# design.net
KiCad netlist of a schematic drawn in Altium Designer
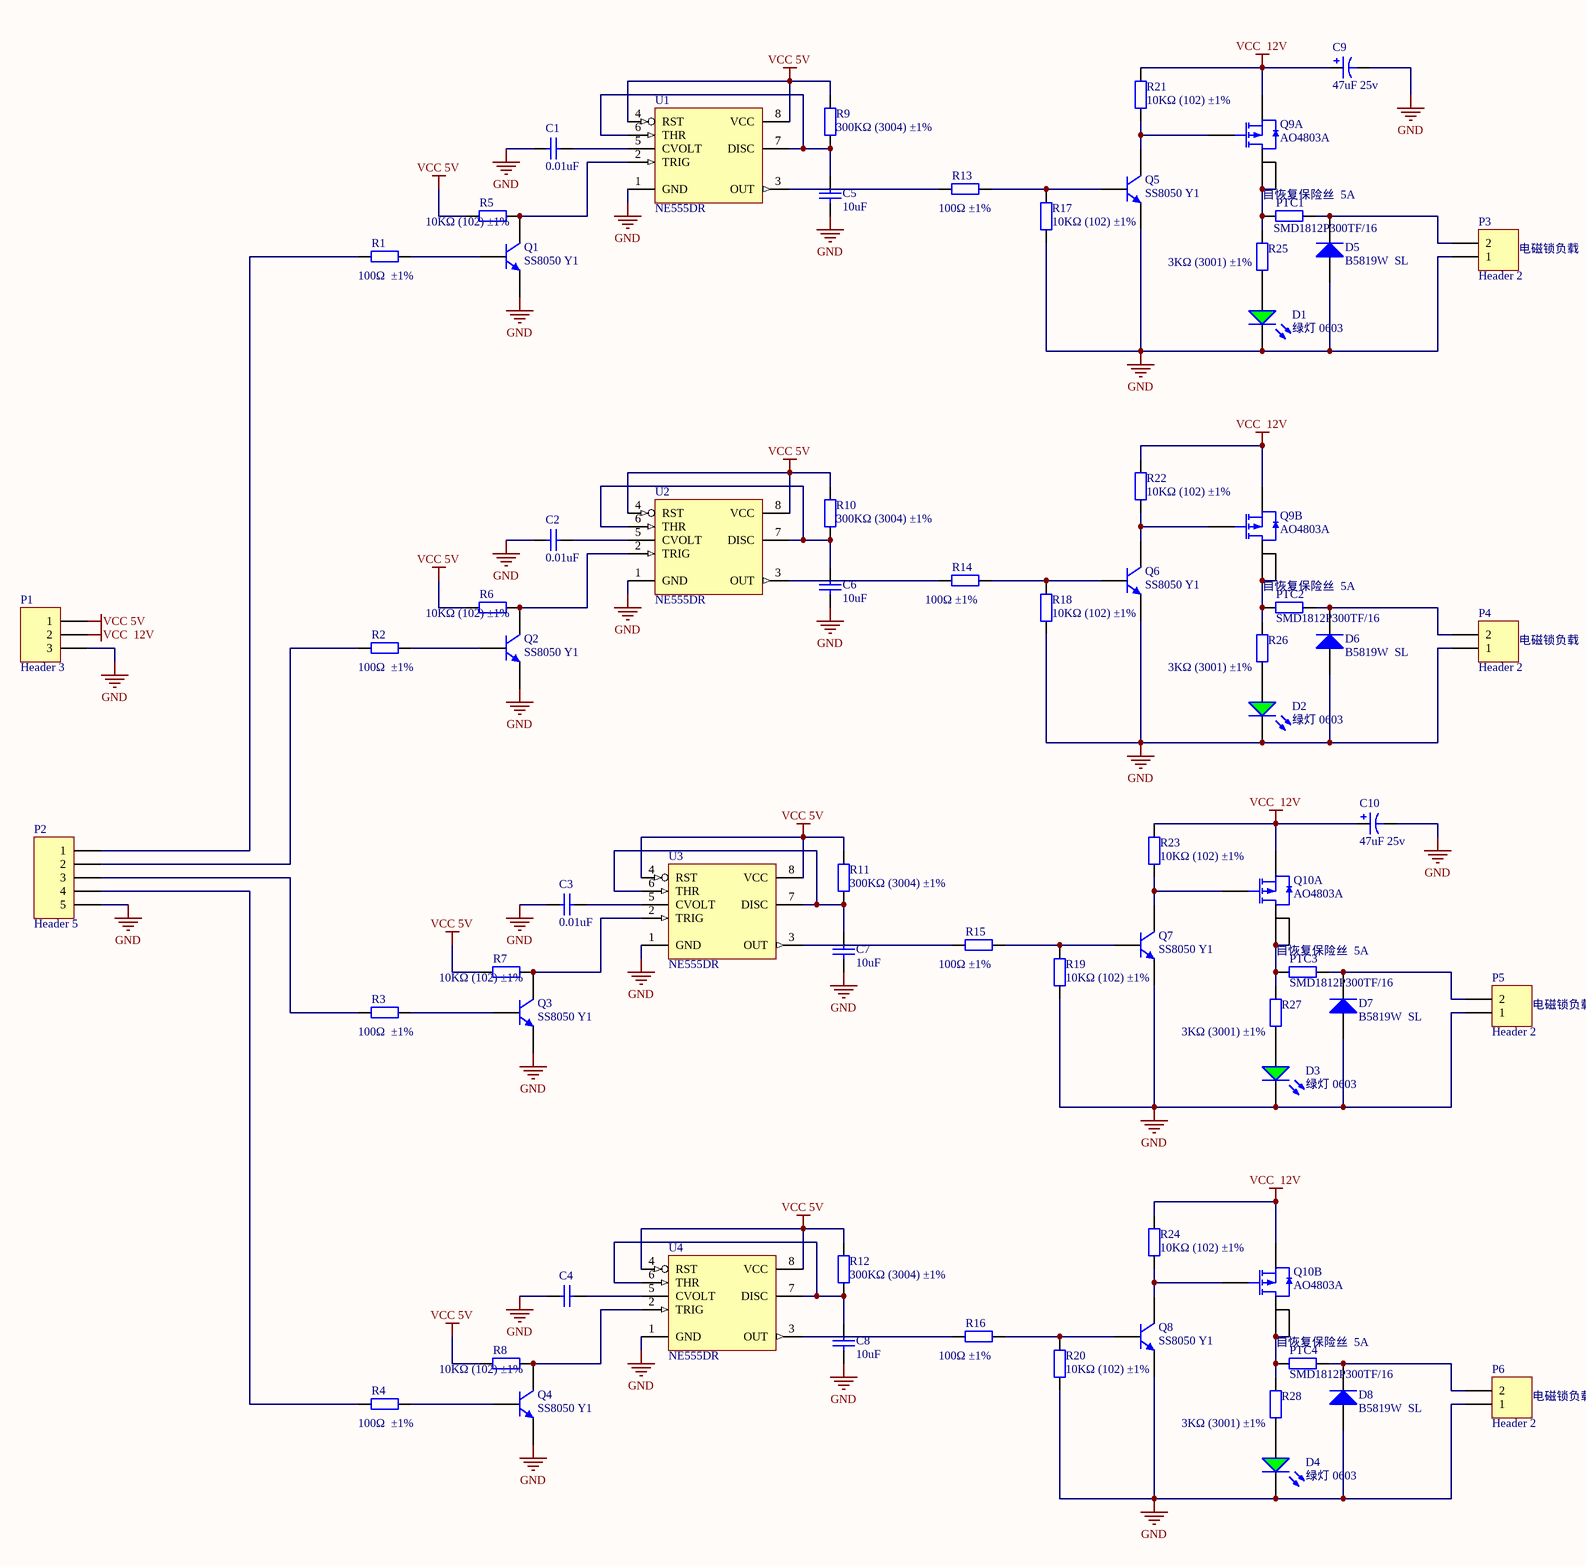
[diagram p0: 电磁阀驱动.SchDoc]

(export (version "E")
  (design (tool "Eeschema 10.0.6"))
  (components
    (comp (ref "C1")
      (value "0.01uF")
      (footprint "0603C")
      (description "Capacitor")
      (fields (field (name "PUBLISHER") "Altium Limited"))
      (libsource (lib "Miscellaneous Devices") (part "Cap"))
    )
    (comp (ref "C2")
      (value "0.01uF")
      (footprint "0603C")
      (description "Capacitor")
      (fields (field (name "PUBLISHER") "Altium Limited"))
      (libsource (lib "Miscellaneous Devices") (part "Cap"))
    )
    (comp (ref "C3")
      (value "0.01uF")
      (footprint "0603C")
      (description "Capacitor")
      (fields (field (name "PUBLISHER") "Altium Limited"))
      (libsource (lib "Miscellaneous Devices") (part "Cap"))
    )
    (comp (ref "C4")
      (value "0.01uF")
      (footprint "0603C")
      (description "Capacitor")
      (fields (field (name "PUBLISHER") "Altium Limited"))
      (libsource (lib "Miscellaneous Devices") (part "Cap"))
    )
    (comp (ref "C5")
      (value "10uF")
      (footprint "0603C")
      (description "Capacitor")
      (fields (field (name "PUBLISHER") "Altium Limited"))
      (libsource (lib "Miscellaneous Devices") (part "Cap"))
    )
    (comp (ref "C6")
      (value "10uF")
      (footprint "0603C")
      (description "Capacitor")
      (fields (field (name "PUBLISHER") "Altium Limited"))
      (libsource (lib "Miscellaneous Devices") (part "Cap"))
    )
    (comp (ref "C7")
      (value "10uF")
      (footprint "0603C")
      (description "Capacitor")
      (fields (field (name "PUBLISHER") "Altium Limited"))
      (libsource (lib "Miscellaneous Devices") (part "Cap"))
    )
    (comp (ref "C8")
      (value "10uF")
      (footprint "0603C")
      (description "Capacitor")
      (fields (field (name "PUBLISHER") "Altium Limited"))
      (libsource (lib "Miscellaneous Devices") (part "Cap"))
    )
    (comp (ref "C9")
      (value "47uF 25v")
      (footprint "CAP_SMD_6*7")
      (description "Polarized Capacitor (Radial)")
      (fields (field (name "PUBLISHER") "Altium Limited"))
      (libsource (lib "Miscellaneous Devices") (part "Cap Pol1"))
    )
    (comp (ref "C10")
      (value "47uF 25v")
      (footprint "CAP_SMD_6*7")
      (description "Polarized Capacitor (Radial)")
      (fields (field (name "PUBLISHER") "Altium Limited"))
      (libsource (lib "Miscellaneous Devices") (part "Cap Pol1"))
    )
    (comp (ref "D1")
      (value "绿灯 0603")
      (footprint "0603_LED_S1")
      (description "发光二极管")
      (libsource (lib "Miscellaneous Devices LC") (part "0603 绿灯"))
    )
    (comp (ref "D2")
      (value "绿灯 0603")
      (footprint "0603_LED_S1")
      (description "发光二极管")
      (libsource (lib "Miscellaneous Devices LC") (part "0603 绿灯"))
    )
    (comp (ref "D3")
      (value "绿灯 0603")
      (footprint "0603_LED_S1")
      (description "发光二极管")
      (libsource (lib "Miscellaneous Devices LC") (part "0603 绿灯"))
    )
    (comp (ref "D4")
      (value "绿灯 0603")
      (footprint "0603_LED_S1")
      (description "发光二极管")
      (libsource (lib "Miscellaneous Devices LC") (part "0603 绿灯"))
    )
    (comp (ref "D5")
      (value "B5819W  SL")
      (footprint "SOD-123")
      (description "肖特基二极管")
      (libsource (lib "Miscellaneous Devices LC") (part "SOD-123 B5819W  SL"))
    )
    (comp (ref "D6")
      (value "B5819W  SL")
      (footprint "SOD-123")
      (description "肖特基二极管")
      (libsource (lib "Miscellaneous Devices LC") (part "SOD-123 B5819W  SL"))
    )
    (comp (ref "D7")
      (value "B5819W  SL")
      (footprint "SOD-123")
      (description "肖特基二极管")
      (libsource (lib "Miscellaneous Devices LC") (part "SOD-123 B5819W  SL"))
    )
    (comp (ref "D8")
      (value "B5819W  SL")
      (footprint "SOD-123")
      (description "肖特基二极管")
      (libsource (lib "Miscellaneous Devices LC") (part "SOD-123 B5819W  SL"))
    )
    (comp (ref "P1")
      (value "Header 3")
      (footprint "sip-3")
      (description "Header, 3-Pin")
      (fields (field (name "PUBLISHER") "Altium Limited"))
      (libsource (lib "Miscellaneous Connectors") (part "Header 3"))
    )
    (comp (ref "P2")
      (value "Header 5")
      (footprint "SIP-5")
      (description "Header, 5-Pin")
      (fields (field (name "PUBLISHER") "Altium Limited"))
      (libsource (lib "Miscellaneous Connectors") (part "Header 5"))
    )
    (comp (ref "P3")
      (value "Header 2")
      (footprint "SIP-2")
      (description "Header, 2-Pin")
      (fields (field (name "PUBLISHER") "Altium Limited"))
      (libsource (lib "Miscellaneous Connectors") (part "Header 2"))
    )
    (comp (ref "P4")
      (value "Header 2")
      (footprint "SIP-2")
      (description "Header, 2-Pin")
      (fields (field (name "PUBLISHER") "Altium Limited"))
      (libsource (lib "Miscellaneous Connectors") (part "Header 2"))
    )
    (comp (ref "P5")
      (value "Header 2")
      (footprint "SIP-2")
      (description "Header, 2-Pin")
      (fields (field (name "PUBLISHER") "Altium Limited"))
      (libsource (lib "Miscellaneous Connectors") (part "Header 2"))
    )
    (comp (ref "P6")
      (value "Header 2")
      (footprint "SIP-2")
      (description "Header, 2-Pin")
      (fields (field (name "PUBLISHER") "Altium Limited"))
      (libsource (lib "Miscellaneous Connectors") (part "Header 2"))
    )
    (comp (ref "PTC1")
      (value "SMD1812P300TF/16")
      (footprint "1812")
      (description "自恢复保险丝")
      (libsource (lib "") (part "0603 3KΩ (3001) 1%_1"))
    )
    (comp (ref "PTC2")
      (value "SMD1812P300TF/16")
      (footprint "1812")
      (description "自恢复保险丝")
      (libsource (lib "") (part "0603 3KΩ (3001) 1%_1"))
    )
    (comp (ref "PTC3")
      (value "SMD1812P300TF/16")
      (footprint "1812")
      (description "自恢复保险丝")
      (libsource (lib "") (part "0603 3KΩ (3001) 1%_1"))
    )
    (comp (ref "PTC4")
      (value "SMD1812P300TF/16")
      (footprint "1812")
      (description "自恢复保险丝")
      (libsource (lib "") (part "0603 3KΩ (3001) 1%_1"))
    )
    (comp (ref "Q1")
      (value "SS8050 Y1")
      (footprint "SOT-23(SOT-23-3)")
      (description "三极管")
      (libsource (lib "Miscellaneous Devices LC") (part "SOT-23 SS8050 Y1"))
    )
    (comp (ref "Q2")
      (value "SS8050 Y1")
      (footprint "SOT-23(SOT-23-3)")
      (description "三极管")
      (libsource (lib "Miscellaneous Devices LC") (part "SOT-23 SS8050 Y1"))
    )
    (comp (ref "Q3")
      (value "SS8050 Y1")
      (footprint "SOT-23(SOT-23-3)")
      (description "三极管")
      (libsource (lib "Miscellaneous Devices LC") (part "SOT-23 SS8050 Y1"))
    )
    (comp (ref "Q4")
      (value "SS8050 Y1")
      (footprint "SOT-23(SOT-23-3)")
      (description "三极管")
      (libsource (lib "Miscellaneous Devices LC") (part "SOT-23 SS8050 Y1"))
    )
    (comp (ref "Q5")
      (value "SS8050 Y1")
      (footprint "SOT-23(SOT-23-3)")
      (description "三极管")
      (libsource (lib "Miscellaneous Devices LC") (part "SOT-23 SS8050 Y1"))
    )
    (comp (ref "Q6")
      (value "SS8050 Y1")
      (footprint "SOT-23(SOT-23-3)")
      (description "三极管")
      (libsource (lib "Miscellaneous Devices LC") (part "SOT-23 SS8050 Y1"))
    )
    (comp (ref "Q7")
      (value "SS8050 Y1")
      (footprint "SOT-23(SOT-23-3)")
      (description "三极管")
      (libsource (lib "Miscellaneous Devices LC") (part "SOT-23 SS8050 Y1"))
    )
    (comp (ref "Q8")
      (value "SS8050 Y1")
      (footprint "SOT-23(SOT-23-3)")
      (description "三极管")
      (libsource (lib "Miscellaneous Devices LC") (part "SOT-23 SS8050 Y1"))
    )
    (comp (ref "Q9")
      (value "AO4803A")
      (footprint "SOP-8_150mil")
      (description "MOS(场效应管)")
      (libsource (lib "Miscellaneous Devices LC") (part "APM4953KC-TRG"))
    )
    (comp (ref "Q10")
      (value "AO4803A")
      (footprint "SOP-8_150mil")
      (description "MOS(场效应管)")
      (libsource (lib "Miscellaneous Devices LC") (part "APM4953KC-TRG"))
    )
    (comp (ref "R1")
      (value "100Ω  ±1%")
      (footprint "0603_R")
      (description "贴片电阻")
      (libsource (lib "Miscellaneous Devices LC") (part "0603 3KΩ (3001) 1%"))
    )
    (comp (ref "R2")
      (value "100Ω  ±1%")
      (footprint "0603_R")
      (description "贴片电阻")
      (libsource (lib "Miscellaneous Devices LC") (part "0603 3KΩ (3001) 1%"))
    )
    (comp (ref "R3")
      (value "100Ω  ±1%")
      (footprint "0603_R")
      (description "贴片电阻")
      (libsource (lib "Miscellaneous Devices LC") (part "0603 3KΩ (3001) 1%"))
    )
    (comp (ref "R4")
      (value "100Ω  ±1%")
      (footprint "0603_R")
      (description "贴片电阻")
      (libsource (lib "Miscellaneous Devices LC") (part "0603 3KΩ (3001) 1%"))
    )
    (comp (ref "R5")
      (value "10KΩ (102) ±1%")
      (footprint "0603_R")
      (description "贴片电阻")
      (libsource (lib "Miscellaneous Devices LC") (part "0603 3KΩ (3001) 1%"))
    )
    (comp (ref "R6")
      (value "10KΩ (102) ±1%")
      (footprint "0603_R")
      (description "贴片电阻")
      (libsource (lib "Miscellaneous Devices LC") (part "0603 3KΩ (3001) 1%"))
    )
    (comp (ref "R7")
      (value "10KΩ (102) ±1%")
      (footprint "0603_R")
      (description "贴片电阻")
      (libsource (lib "Miscellaneous Devices LC") (part "0603 3KΩ (3001) 1%"))
    )
    (comp (ref "R8")
      (value "10KΩ (102) ±1%")
      (footprint "0603_R")
      (description "贴片电阻")
      (libsource (lib "Miscellaneous Devices LC") (part "0603 3KΩ (3001) 1%"))
    )
    (comp (ref "R9")
      (value "300KΩ (3004) ±1%")
      (footprint "0603_R")
      (description "贴片电阻")
      (libsource (lib "") (part "0603 3KΩ (3001) 1%_2"))
    )
    (comp (ref "R10")
      (value "300KΩ (3004) ±1%")
      (footprint "0603_R")
      (description "贴片电阻")
      (libsource (lib "") (part "0603 3KΩ (3001) 1%_2"))
    )
    (comp (ref "R11")
      (value "300KΩ (3004) ±1%")
      (footprint "0603_R")
      (description "贴片电阻")
      (libsource (lib "") (part "0603 3KΩ (3001) 1%_2"))
    )
    (comp (ref "R12")
      (value "300KΩ (3004) ±1%")
      (footprint "0603_R")
      (description "贴片电阻")
      (libsource (lib "") (part "0603 3KΩ (3001) 1%_2"))
    )
    (comp (ref "R13")
      (value "100Ω ±1%")
      (footprint "0603_R")
      (description "贴片电阻")
      (libsource (lib "") (part "0603 3KΩ (3001) 1%_1"))
    )
    (comp (ref "R14")
      (value "100Ω ±1%")
      (footprint "0603_R")
      (description "贴片电阻")
      (libsource (lib "") (part "0603 3KΩ (3001) 1%_1"))
    )
    (comp (ref "R15")
      (value "100Ω ±1%")
      (footprint "0603_R")
      (description "贴片电阻")
      (libsource (lib "") (part "0603 3KΩ (3001) 1%_1"))
    )
    (comp (ref "R16")
      (value "100Ω ±1%")
      (footprint "0603_R")
      (description "贴片电阻")
      (libsource (lib "") (part "0603 3KΩ (3001) 1%_1"))
    )
    (comp (ref "R17")
      (value "10KΩ (102) ±1%")
      (footprint "0603_R")
      (description "贴片电阻")
      (libsource (lib "") (part "0603 3KΩ (3001) 1%_3"))
    )
    (comp (ref "R18")
      (value "10KΩ (102) ±1%")
      (footprint "0603_R")
      (description "贴片电阻")
      (libsource (lib "") (part "0603 3KΩ (3001) 1%_3"))
    )
    (comp (ref "R19")
      (value "10KΩ (102) ±1%")
      (footprint "0603_R")
      (description "贴片电阻")
      (libsource (lib "") (part "0603 3KΩ (3001) 1%_3"))
    )
    (comp (ref "R20")
      (value "10KΩ (102) ±1%")
      (footprint "0603_R")
      (description "贴片电阻")
      (libsource (lib "") (part "0603 3KΩ (3001) 1%_3"))
    )
    (comp (ref "R21")
      (value "10KΩ (102) ±1%")
      (footprint "0603_R")
      (description "贴片电阻")
      (libsource (lib "") (part "0603 3KΩ (3001) 1%_3"))
    )
    (comp (ref "R22")
      (value "10KΩ (102) ±1%")
      (footprint "0603_R")
      (description "贴片电阻")
      (libsource (lib "") (part "0603 3KΩ (3001) 1%_3"))
    )
    (comp (ref "R23")
      (value "10KΩ (102) ±1%")
      (footprint "0603_R")
      (description "贴片电阻")
      (libsource (lib "") (part "0603 3KΩ (3001) 1%_3"))
    )
    (comp (ref "R24")
      (value "10KΩ (102) ±1%")
      (footprint "0603_R")
      (description "贴片电阻")
      (libsource (lib "") (part "0603 3KΩ (3001) 1%_3"))
    )
    (comp (ref "R25")
      (value "3KΩ (3001) ±1%")
      (footprint "0603_R")
      (description "贴片电阻")
      (libsource (lib "") (part "0603 3KΩ (3001) 1%_2"))
    )
    (comp (ref "R26")
      (value "3KΩ (3001) ±1%")
      (footprint "0603_R")
      (description "贴片电阻")
      (libsource (lib "") (part "0603 3KΩ (3001) 1%_2"))
    )
    (comp (ref "R27")
      (value "3KΩ (3001) ±1%")
      (footprint "0603_R")
      (description "贴片电阻")
      (libsource (lib "") (part "0603 3KΩ (3001) 1%_2"))
    )
    (comp (ref "R28")
      (value "3KΩ (3001) ±1%")
      (footprint "0603_R")
      (description "贴片电阻")
      (libsource (lib "") (part "0603 3KΩ (3001) 1%_2"))
    )
    (comp (ref "U1")
      (value "NE555DR")
      (footprint "SOIC-8_150mil")
      (description "时基集成")
      (libsource (lib "Miscellaneous Devices LC") (part "NE555DR_[C7593]"))
    )
    (comp (ref "U2")
      (value "NE555DR")
      (footprint "SOIC-8_150mil")
      (description "时基集成")
      (libsource (lib "Miscellaneous Devices LC") (part "NE555DR_[C7593]"))
    )
    (comp (ref "U3")
      (value "NE555DR")
      (footprint "SOIC-8_150mil")
      (description "时基集成")
      (libsource (lib "Miscellaneous Devices LC") (part "NE555DR_[C7593]"))
    )
    (comp (ref "U4")
      (value "NE555DR")
      (footprint "SOIC-8_150mil")
      (description "时基集成")
      (libsource (lib "Miscellaneous Devices LC") (part "NE555DR_[C7593]"))
    )
  )
  (nets
    (net (code "1") (name "GND") (class "Default")
      (node (ref "C1") (pin "1") (pinfunction "1_1") (pintype "passive"))
      (node (ref "C10") (pin "2") (pinfunction "2_2") (pintype "passive"))
      (node (ref "C2") (pin "1") (pinfunction "1_1") (pintype "passive"))
      (node (ref "C3") (pin "1") (pinfunction "1_1") (pintype "passive"))
      (node (ref "C4") (pin "1") (pinfunction "1_1") (pintype "passive"))
      (node (ref "C5") (pin "1") (pinfunction "1_1") (pintype "passive"))
      (node (ref "C6") (pin "1") (pinfunction "1_1") (pintype "passive"))
      (node (ref "C7") (pin "1") (pinfunction "1_1") (pintype "passive"))
      (node (ref "C8") (pin "1") (pinfunction "1_1") (pintype "passive"))
      (node (ref "C9") (pin "2") (pinfunction "2_2") (pintype "passive"))
      (node (ref "D1") (pin "K") (pinfunction "K_K") (pintype "passive"))
      (node (ref "D2") (pin "K") (pinfunction "K_K") (pintype "passive"))
      (node (ref "D3") (pin "K") (pinfunction "K_K") (pintype "passive"))
      (node (ref "D4") (pin "K") (pinfunction "K_K") (pintype "passive"))
      (node (ref "D5") (pin "1") (pinfunction "A_1") (pintype "passive"))
      (node (ref "D6") (pin "1") (pinfunction "A_1") (pintype "passive"))
      (node (ref "D7") (pin "1") (pinfunction "A_1") (pintype "passive"))
      (node (ref "D8") (pin "1") (pinfunction "A_1") (pintype "passive"))
      (node (ref "P1") (pin "3") (pinfunction "3_3") (pintype "passive"))
      (node (ref "P2") (pin "5") (pinfunction "5_5") (pintype "passive"))
      (node (ref "P3") (pin "1") (pinfunction "1_1") (pintype "passive"))
      (node (ref "P4") (pin "1") (pinfunction "1_1") (pintype "passive"))
      (node (ref "P5") (pin "1") (pinfunction "1_1") (pintype "passive"))
      (node (ref "P6") (pin "1") (pinfunction "1_1") (pintype "passive"))
      (node (ref "Q1") (pin "2") (pinfunction "E_2") (pintype "passive"))
      (node (ref "Q2") (pin "2") (pinfunction "E_2") (pintype "passive"))
      (node (ref "Q3") (pin "2") (pinfunction "E_2") (pintype "passive"))
      (node (ref "Q4") (pin "2") (pinfunction "E_2") (pintype "passive"))
      (node (ref "Q5") (pin "2") (pinfunction "E_2") (pintype "passive"))
      (node (ref "Q6") (pin "2") (pinfunction "E_2") (pintype "passive"))
      (node (ref "Q7") (pin "2") (pinfunction "E_2") (pintype "passive"))
      (node (ref "Q8") (pin "2") (pinfunction "E_2") (pintype "passive"))
      (node (ref "R17") (pin "1") (pinfunction "1_1") (pintype "passive"))
      (node (ref "R18") (pin "1") (pinfunction "1_1") (pintype "passive"))
      (node (ref "R19") (pin "1") (pinfunction "1_1") (pintype "passive"))
      (node (ref "R20") (pin "1") (pinfunction "1_1") (pintype "passive"))
      (node (ref "U1") (pin "1") (pinfunction "GND_1") (pintype "power_in"))
      (node (ref "U2") (pin "1") (pinfunction "GND_1") (pintype "power_in"))
      (node (ref "U3") (pin "1") (pinfunction "GND_1") (pintype "power_in"))
      (node (ref "U4") (pin "1") (pinfunction "GND_1") (pintype "power_in"))
    )
    (net (code "2") (name "Net-(D1-PadA)") (class "Default")
      (node (ref "D1") (pin "A") (pinfunction "A_A") (pintype "passive"))
      (node (ref "R25") (pin "2") (pinfunction "2_2") (pintype "passive"))
    )
    (net (code "3") (name "Net-(D2-PadA)") (class "Default")
      (node (ref "D2") (pin "A") (pinfunction "A_A") (pintype "passive"))
      (node (ref "R26") (pin "2") (pinfunction "2_2") (pintype "passive"))
    )
    (net (code "4") (name "Net-(D3-PadA)") (class "Default")
      (node (ref "D3") (pin "A") (pinfunction "A_A") (pintype "passive"))
      (node (ref "R27") (pin "2") (pinfunction "2_2") (pintype "passive"))
    )
    (net (code "5") (name "Net-(D4-PadA)") (class "Default")
      (node (ref "D4") (pin "A") (pinfunction "A_A") (pintype "passive"))
      (node (ref "R28") (pin "2") (pinfunction "2_2") (pintype "passive"))
    )
    (net (code "6") (name "Net-(D5-K)") (class "Default")
      (node (ref "D5") (pin "2") (pinfunction "K_2") (pintype "passive"))
      (node (ref "P3") (pin "2") (pinfunction "2_2") (pintype "passive"))
      (node (ref "PTC1") (pin "2") (pinfunction "2_2") (pintype "passive"))
    )
    (net (code "7") (name "Net-(D6-K)") (class "Default")
      (node (ref "D6") (pin "2") (pinfunction "K_2") (pintype "passive"))
      (node (ref "P4") (pin "2") (pinfunction "2_2") (pintype "passive"))
      (node (ref "PTC2") (pin "2") (pinfunction "2_2") (pintype "passive"))
    )
    (net (code "8") (name "Net-(D7-K)") (class "Default")
      (node (ref "D7") (pin "2") (pinfunction "K_2") (pintype "passive"))
      (node (ref "P5") (pin "2") (pinfunction "2_2") (pintype "passive"))
      (node (ref "PTC3") (pin "2") (pinfunction "2_2") (pintype "passive"))
    )
    (net (code "9") (name "Net-(D8-K)") (class "Default")
      (node (ref "D8") (pin "2") (pinfunction "K_2") (pintype "passive"))
      (node (ref "P6") (pin "2") (pinfunction "2_2") (pintype "passive"))
      (node (ref "PTC4") (pin "2") (pinfunction "2_2") (pintype "passive"))
    )
    (net (code "10") (name "Net-(P2-Pad1)") (class "Default")
      (node (ref "P2") (pin "1") (pinfunction "1_1") (pintype "passive"))
      (node (ref "R1") (pin "2") (pinfunction "2_2") (pintype "passive"))
    )
    (net (code "11") (name "Net-(P2-Pad2)") (class "Default")
      (node (ref "P2") (pin "2") (pinfunction "2_2") (pintype "passive"))
      (node (ref "R2") (pin "2") (pinfunction "2_2") (pintype "passive"))
    )
    (net (code "12") (name "Net-(P2-Pad3)") (class "Default")
      (node (ref "P2") (pin "3") (pinfunction "3_3") (pintype "passive"))
      (node (ref "R3") (pin "2") (pinfunction "2_2") (pintype "passive"))
    )
    (net (code "13") (name "Net-(P2-Pad4)") (class "Default")
      (node (ref "P2") (pin "4") (pinfunction "4_4") (pintype "passive"))
      (node (ref "R4") (pin "2") (pinfunction "2_2") (pintype "passive"))
    )
    (net (code "14") (name "Net-(PTC1-Pad1)") (class "Default")
      (node (ref "PTC1") (pin "1") (pinfunction "1_1") (pintype "passive"))
      (node (ref "Q9") (pin "7") (pinfunction "D_7") (pintype "passive"))
      (node (ref "Q9") (pin "8") (pinfunction "D_8") (pintype "passive"))
      (node (ref "R25") (pin "1") (pinfunction "1_1") (pintype "passive"))
    )
    (net (code "15") (name "Net-(PTC2-Pad1)") (class "Default")
      (node (ref "PTC2") (pin "1") (pinfunction "1_1") (pintype "passive"))
      (node (ref "Q9") (pin "5") (pinfunction "D_5") (pintype "passive"))
      (node (ref "Q9") (pin "6") (pinfunction "D_6") (pintype "passive"))
      (node (ref "R26") (pin "1") (pinfunction "1_1") (pintype "passive"))
    )
    (net (code "16") (name "Net-(PTC3-Pad1)") (class "Default")
      (node (ref "PTC3") (pin "1") (pinfunction "1_1") (pintype "passive"))
      (node (ref "Q10") (pin "7") (pinfunction "D_7") (pintype "passive"))
      (node (ref "Q10") (pin "8") (pinfunction "D_8") (pintype "passive"))
      (node (ref "R27") (pin "1") (pinfunction "1_1") (pintype "passive"))
    )
    (net (code "17") (name "Net-(PTC4-Pad1)") (class "Default")
      (node (ref "PTC4") (pin "1") (pinfunction "1_1") (pintype "passive"))
      (node (ref "Q10") (pin "5") (pinfunction "D_5") (pintype "passive"))
      (node (ref "Q10") (pin "6") (pinfunction "D_6") (pintype "passive"))
      (node (ref "R28") (pin "1") (pinfunction "1_1") (pintype "passive"))
    )
    (net (code "18") (name "Net-(Q1-B)") (class "Default")
      (node (ref "Q1") (pin "1") (pinfunction "B_1") (pintype "passive"))
      (node (ref "R1") (pin "1") (pinfunction "1_1") (pintype "passive"))
    )
    (net (code "19") (name "Net-(Q1-C)") (class "Default")
      (node (ref "Q1") (pin "3") (pinfunction "C_3") (pintype "passive"))
      (node (ref "R5") (pin "1") (pinfunction "1_1") (pintype "passive"))
      (node (ref "U1") (pin "2") (pinfunction "TRIG_2") (pintype "input"))
    )
    (net (code "20") (name "Net-(Q2-B)") (class "Default")
      (node (ref "Q2") (pin "1") (pinfunction "B_1") (pintype "passive"))
      (node (ref "R2") (pin "1") (pinfunction "1_1") (pintype "passive"))
    )
    (net (code "21") (name "Net-(Q2-C)") (class "Default")
      (node (ref "Q2") (pin "3") (pinfunction "C_3") (pintype "passive"))
      (node (ref "R6") (pin "1") (pinfunction "1_1") (pintype "passive"))
      (node (ref "U2") (pin "2") (pinfunction "TRIG_2") (pintype "input"))
    )
    (net (code "22") (name "Net-(Q3-B)") (class "Default")
      (node (ref "Q3") (pin "1") (pinfunction "B_1") (pintype "passive"))
      (node (ref "R3") (pin "1") (pinfunction "1_1") (pintype "passive"))
    )
    (net (code "23") (name "Net-(Q3-C)") (class "Default")
      (node (ref "Q3") (pin "3") (pinfunction "C_3") (pintype "passive"))
      (node (ref "R7") (pin "1") (pinfunction "1_1") (pintype "passive"))
      (node (ref "U3") (pin "2") (pinfunction "TRIG_2") (pintype "input"))
    )
    (net (code "24") (name "Net-(Q4-B)") (class "Default")
      (node (ref "Q4") (pin "1") (pinfunction "B_1") (pintype "passive"))
      (node (ref "R4") (pin "1") (pinfunction "1_1") (pintype "passive"))
    )
    (net (code "25") (name "Net-(Q4-C)") (class "Default")
      (node (ref "Q4") (pin "3") (pinfunction "C_3") (pintype "passive"))
      (node (ref "R8") (pin "1") (pinfunction "1_1") (pintype "passive"))
      (node (ref "U4") (pin "2") (pinfunction "TRIG_2") (pintype "input"))
    )
    (net (code "26") (name "Net-(Q5-B)") (class "Default")
      (node (ref "Q5") (pin "1") (pinfunction "B_1") (pintype "passive"))
      (node (ref "R13") (pin "2") (pinfunction "2_2") (pintype "passive"))
      (node (ref "R17") (pin "2") (pinfunction "2_2") (pintype "passive"))
    )
    (net (code "27") (name "Net-(Q5-C)") (class "Default")
      (node (ref "Q5") (pin "3") (pinfunction "C_3") (pintype "passive"))
      (node (ref "Q9") (pin "2") (pinfunction "G_2") (pintype "passive"))
      (node (ref "R21") (pin "1") (pinfunction "1_1") (pintype "passive"))
    )
    (net (code "28") (name "Net-(Q6-B)") (class "Default")
      (node (ref "Q6") (pin "1") (pinfunction "B_1") (pintype "passive"))
      (node (ref "R14") (pin "2") (pinfunction "2_2") (pintype "passive"))
      (node (ref "R18") (pin "2") (pinfunction "2_2") (pintype "passive"))
    )
    (net (code "29") (name "Net-(Q6-C)") (class "Default")
      (node (ref "Q6") (pin "3") (pinfunction "C_3") (pintype "passive"))
      (node (ref "Q9") (pin "4") (pinfunction "G_4") (pintype "passive"))
      (node (ref "R22") (pin "1") (pinfunction "1_1") (pintype "passive"))
    )
    (net (code "30") (name "Net-(Q7-B)") (class "Default")
      (node (ref "Q7") (pin "1") (pinfunction "B_1") (pintype "passive"))
      (node (ref "R15") (pin "2") (pinfunction "2_2") (pintype "passive"))
      (node (ref "R19") (pin "2") (pinfunction "2_2") (pintype "passive"))
    )
    (net (code "31") (name "Net-(Q8-B)") (class "Default")
      (node (ref "Q8") (pin "1") (pinfunction "B_1") (pintype "passive"))
      (node (ref "R16") (pin "2") (pinfunction "2_2") (pintype "passive"))
      (node (ref "R20") (pin "2") (pinfunction "2_2") (pintype "passive"))
    )
    (net (code "32") (name "Net-(Q10A-G)") (class "Default")
      (node (ref "Q10") (pin "2") (pinfunction "G_2") (pintype "passive"))
      (node (ref "Q7") (pin "3") (pinfunction "C_3") (pintype "passive"))
      (node (ref "R23") (pin "1") (pinfunction "1_1") (pintype "passive"))
    )
    (net (code "33") (name "Net-(Q10B-G)") (class "Default")
      (node (ref "Q10") (pin "4") (pinfunction "G_4") (pintype "passive"))
      (node (ref "Q8") (pin "3") (pinfunction "C_3") (pintype "passive"))
      (node (ref "R24") (pin "1") (pinfunction "1_1") (pintype "passive"))
    )
    (net (code "34") (name "Net-(U1-CVOLT)") (class "Default")
      (node (ref "C1") (pin "2") (pinfunction "2_2") (pintype "passive"))
      (node (ref "U1") (pin "5") (pinfunction "CVOLT_5") (pintype "passive"))
    )
    (net (code "35") (name "Net-(U1-DISC)") (class "Default")
      (node (ref "C5") (pin "2") (pinfunction "2_2") (pintype "passive"))
      (node (ref "R9") (pin "2") (pinfunction "2_2") (pintype "passive"))
      (node (ref "U1") (pin "6") (pinfunction "THR_6") (pintype "input"))
      (node (ref "U1") (pin "7") (pinfunction "DISC_7") (pintype "open_collector"))
    )
    (net (code "36") (name "Net-(U1-OUT)") (class "Default")
      (node (ref "R13") (pin "1") (pinfunction "1_1") (pintype "passive"))
      (node (ref "U1") (pin "3") (pinfunction "OUT_3") (pintype "output"))
    )
    (net (code "37") (name "Net-(U2-CVOLT)") (class "Default")
      (node (ref "C2") (pin "2") (pinfunction "2_2") (pintype "passive"))
      (node (ref "U2") (pin "5") (pinfunction "CVOLT_5") (pintype "passive"))
    )
    (net (code "38") (name "Net-(U2-DISC)") (class "Default")
      (node (ref "C6") (pin "2") (pinfunction "2_2") (pintype "passive"))
      (node (ref "R10") (pin "2") (pinfunction "2_2") (pintype "passive"))
      (node (ref "U2") (pin "6") (pinfunction "THR_6") (pintype "input"))
      (node (ref "U2") (pin "7") (pinfunction "DISC_7") (pintype "open_collector"))
    )
    (net (code "39") (name "Net-(U2-OUT)") (class "Default")
      (node (ref "R14") (pin "1") (pinfunction "1_1") (pintype "passive"))
      (node (ref "U2") (pin "3") (pinfunction "OUT_3") (pintype "output"))
    )
    (net (code "40") (name "Net-(U3-CVOLT)") (class "Default")
      (node (ref "C3") (pin "2") (pinfunction "2_2") (pintype "passive"))
      (node (ref "U3") (pin "5") (pinfunction "CVOLT_5") (pintype "passive"))
    )
    (net (code "41") (name "Net-(U3-DISC)") (class "Default")
      (node (ref "C7") (pin "2") (pinfunction "2_2") (pintype "passive"))
      (node (ref "R11") (pin "2") (pinfunction "2_2") (pintype "passive"))
      (node (ref "U3") (pin "6") (pinfunction "THR_6") (pintype "input"))
      (node (ref "U3") (pin "7") (pinfunction "DISC_7") (pintype "open_collector"))
    )
    (net (code "42") (name "Net-(U3-OUT)") (class "Default")
      (node (ref "R15") (pin "1") (pinfunction "1_1") (pintype "passive"))
      (node (ref "U3") (pin "3") (pinfunction "OUT_3") (pintype "output"))
    )
    (net (code "43") (name "Net-(U4-CVOLT)") (class "Default")
      (node (ref "C4") (pin "2") (pinfunction "2_2") (pintype "passive"))
      (node (ref "U4") (pin "5") (pinfunction "CVOLT_5") (pintype "passive"))
    )
    (net (code "44") (name "Net-(U4-DISC)") (class "Default")
      (node (ref "C8") (pin "2") (pinfunction "2_2") (pintype "passive"))
      (node (ref "R12") (pin "2") (pinfunction "2_2") (pintype "passive"))
      (node (ref "U4") (pin "6") (pinfunction "THR_6") (pintype "input"))
      (node (ref "U4") (pin "7") (pinfunction "DISC_7") (pintype "open_collector"))
    )
    (net (code "45") (name "Net-(U4-OUT)") (class "Default")
      (node (ref "R16") (pin "1") (pinfunction "1_1") (pintype "passive"))
      (node (ref "U4") (pin "3") (pinfunction "OUT_3") (pintype "output"))
    )
    (net (code "46") (name "VCC  12V") (class "Default")
      (node (ref "C10") (pin "1") (pinfunction "1_1") (pintype "passive"))
      (node (ref "C9") (pin "1") (pinfunction "1_1") (pintype "passive"))
      (node (ref "P1") (pin "2") (pinfunction "2_2") (pintype "passive"))
      (node (ref "Q10") (pin "1") (pinfunction "S_1") (pintype "passive"))
      (node (ref "Q10") (pin "3") (pinfunction "S_3") (pintype "passive"))
      (node (ref "Q9") (pin "1") (pinfunction "S_1") (pintype "passive"))
      (node (ref "Q9") (pin "3") (pinfunction "S_3") (pintype "passive"))
      (node (ref "R21") (pin "2") (pinfunction "2_2") (pintype "passive"))
      (node (ref "R22") (pin "2") (pinfunction "2_2") (pintype "passive"))
      (node (ref "R23") (pin "2") (pinfunction "2_2") (pintype "passive"))
      (node (ref "R24") (pin "2") (pinfunction "2_2") (pintype "passive"))
    )
    (net (code "47") (name "VCC 5V") (class "Default")
      (node (ref "P1") (pin "1") (pinfunction "1_1") (pintype "passive"))
      (node (ref "R10") (pin "1") (pinfunction "1_1") (pintype "passive"))
      (node (ref "R11") (pin "1") (pinfunction "1_1") (pintype "passive"))
      (node (ref "R12") (pin "1") (pinfunction "1_1") (pintype "passive"))
      (node (ref "R5") (pin "2") (pinfunction "2_2") (pintype "passive"))
      (node (ref "R6") (pin "2") (pinfunction "2_2") (pintype "passive"))
      (node (ref "R7") (pin "2") (pinfunction "2_2") (pintype "passive"))
      (node (ref "R8") (pin "2") (pinfunction "2_2") (pintype "passive"))
      (node (ref "R9") (pin "1") (pinfunction "1_1") (pintype "passive"))
      (node (ref "U1") (pin "4") (pinfunction "RST_4") (pintype "input"))
      (node (ref "U1") (pin "8") (pinfunction "VCC_8") (pintype "power_in"))
      (node (ref "U2") (pin "4") (pinfunction "RST_4") (pintype "input"))
      (node (ref "U2") (pin "8") (pinfunction "VCC_8") (pintype "power_in"))
      (node (ref "U3") (pin "4") (pinfunction "RST_4") (pintype "input"))
      (node (ref "U3") (pin "8") (pinfunction "VCC_8") (pintype "power_in"))
      (node (ref "U4") (pin "4") (pinfunction "RST_4") (pintype "input"))
      (node (ref "U4") (pin "8") (pinfunction "VCC_8") (pintype "power_in"))
    )
  )
)
